# P4.net
KiCad netlist of a schematic drawn in Altium Designer
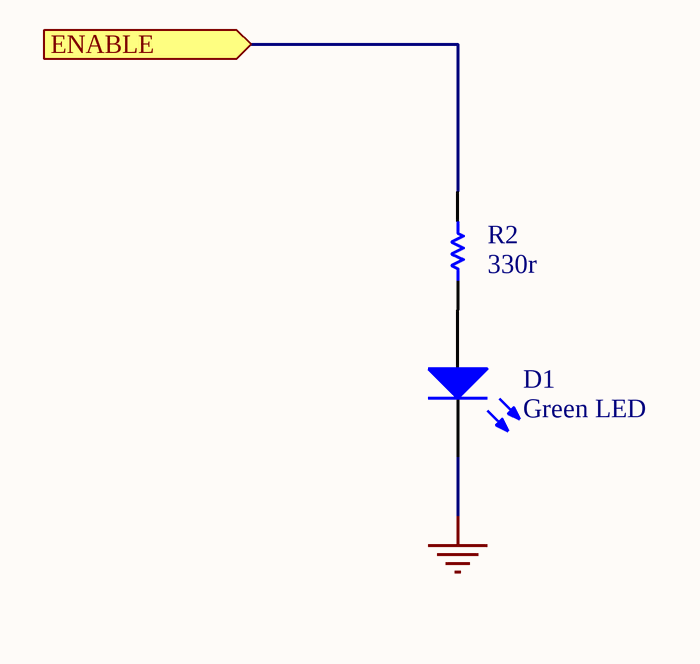
[diagram p0: P4.SchDoc]

(export (version "E")
  (design (tool "Eeschema 10.0.6"))
  (components
    (comp (ref "D1")
      (value "Green LED")
      (footprint "LED-0")
      (description "Typical INFRARED GaAs LED")
      (fields (field (name "PUBLISHER") "Altium Limited"))
      (libsource (lib "Miscellaneous Devices") (part "LED0"))
    )
    (comp (ref "R2")
      (value "330r")
      (footprint "AXIAL-0.3")
      (description "Resistor")
      (fields (field (name "Comment") "Res1") (field (name "PUBLISHER") "Altium Limited"))
      (libsource (lib "Miscellaneous Devices") (part "Res1"))
    )
  )
  (nets
    (net (code "1") (name "/ENABLE") (class "Default")
      (node (ref "R2") (pin "2") (pinfunction "2_2") (pintype "passive"))
    )
    (net (code "2") (name "GND") (class "Default")
      (node (ref "D1") (pin "2") (pinfunction "K_2") (pintype "passive"))
    )
    (net (code "3") (name "Net-(D1-A)") (class "Default")
      (node (ref "D1") (pin "1") (pinfunction "A_1") (pintype "passive"))
      (node (ref "R2") (pin "1") (pinfunction "1_1") (pintype "passive"))
    )
  )
)
